# hall_shield.net
KiCad netlist of a schematic drawn in EAGLE
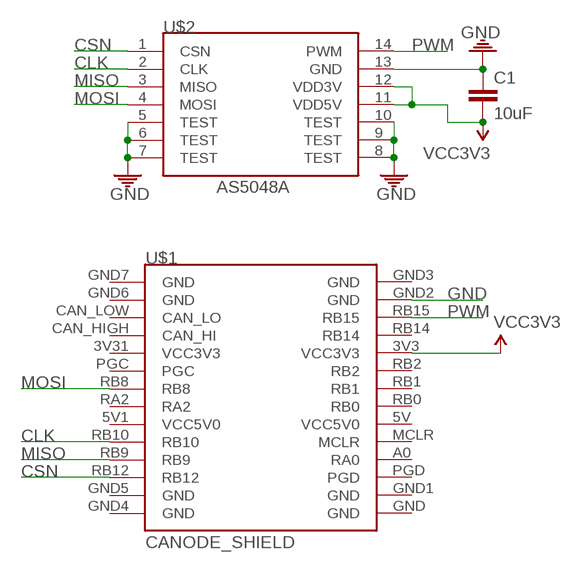
[diagram p0: schematic, sheet 1]

(export (version "E")
  (design (tool "Eeschema 10.0.6"))
  (components
    (comp (ref "C1")
      (value "10uF")
      (footprint "eagle-import:1206")
      (libsource (lib "eagle-import") (part "CAP1206"))
    )
    (comp (ref "U$1")
      (value "CANODE_SHIELD")
      (footprint "eagle-import:CANODE_SHIELD")
      (libsource (lib "eagle-import") (part "CANODE_SHIELD"))
    )
    (comp (ref "U$2")
      (value "AS5048A")
      (footprint "eagle-import:TSSOP14")
      (libsource (lib "eagle-import") (part "AS5048A"))
    )
  )
  (nets
    (net (code "1") (name "/CLK") (class "Default")
      (node (ref "U$1") (pin "RB10") (pinfunction "RB10_RB10") (pintype "bidirectional"))
      (node (ref "U$2") (pin "2") (pinfunction "CLK_2") (pintype "bidirectional"))
    )
    (net (code "2") (name "/CSN") (class "Default")
      (node (ref "U$1") (pin "RB12") (pinfunction "RB12_RB12") (pintype "bidirectional"))
      (node (ref "U$2") (pin "1") (pinfunction "CSN_1") (pintype "bidirectional"))
    )
    (net (code "3") (name "/MISO") (class "Default")
      (node (ref "U$1") (pin "RB9") (pinfunction "RB9_RB9") (pintype "bidirectional"))
      (node (ref "U$2") (pin "3") (pinfunction "MISO_3") (pintype "bidirectional"))
    )
    (net (code "4") (name "/MOSI") (class "Default")
      (node (ref "U$1") (pin "RB8") (pinfunction "RB8_RB8") (pintype "bidirectional"))
      (node (ref "U$2") (pin "4") (pinfunction "MOSI_4") (pintype "bidirectional"))
    )
    (net (code "5") (name "/PWM") (class "Default")
      (node (ref "U$1") (pin "RB15") (pinfunction "RB15_RB15") (pintype "bidirectional"))
      (node (ref "U$2") (pin "14") (pinfunction "PWM_14") (pintype "bidirectional"))
    )
    (net (code "6") (name "GND") (class "Default")
      (node (ref "C1") (pin "1") (pinfunction "1_1") (pintype "passive"))
      (node (ref "U$1") (pin "GND2") (pinfunction "GND_GND2") (pintype "bidirectional"))
      (node (ref "U$2") (pin "10") (pinfunction "TEST_10") (pintype "bidirectional"))
      (node (ref "U$2") (pin "13") (pinfunction "GND_13") (pintype "bidirectional"))
      (node (ref "U$2") (pin "5") (pinfunction "TEST_5") (pintype "bidirectional"))
      (node (ref "U$2") (pin "6") (pinfunction "TEST_6") (pintype "bidirectional"))
      (node (ref "U$2") (pin "7") (pinfunction "TEST_7") (pintype "bidirectional"))
      (node (ref "U$2") (pin "8") (pinfunction "TEST_8") (pintype "bidirectional"))
      (node (ref "U$2") (pin "9") (pinfunction "TEST_9") (pintype "bidirectional"))
    )
    (net (code "7") (name "VCC3V3") (class "Default")
      (node (ref "C1") (pin "2") (pinfunction "2_2") (pintype "passive"))
      (node (ref "U$1") (pin "3V3") (pinfunction "VCC3V3_3V3") (pintype "bidirectional"))
      (node (ref "U$2") (pin "11") (pinfunction "VDD5V_11") (pintype "bidirectional"))
      (node (ref "U$2") (pin "12") (pinfunction "VDD3V_12") (pintype "bidirectional"))
    )
    (net (code "8") (name "unconnected-(U$1-CAN_HI-PadCAN_HIGH)") (class "Default")
      (node (ref "U$1") (pin "CAN_HIGH") (pinfunction "CAN_HI_CAN_HIGH") (pintype "bidirectional"))
    )
    (net (code "9") (name "unconnected-(U$1-CAN_LO-PadCAN_LOW)") (class "Default")
      (node (ref "U$1") (pin "CAN_LOW") (pinfunction "CAN_LO_CAN_LOW") (pintype "bidirectional"))
    )
    (net (code "10") (name "unconnected-(U$1-GND-PadGND1)") (class "Default")
      (node (ref "U$1") (pin "GND1") (pinfunction "GND_GND1") (pintype "bidirectional"))
    )
    (net (code "11") (name "unconnected-(U$1-GND-PadGND3)") (class "Default")
      (node (ref "U$1") (pin "GND3") (pinfunction "GND_GND3") (pintype "bidirectional"))
    )
    (net (code "12") (name "unconnected-(U$1-GND-PadGND4)") (class "Default")
      (node (ref "U$1") (pin "GND4") (pinfunction "GND_GND4") (pintype "bidirectional"))
    )
    (net (code "13") (name "unconnected-(U$1-GND-PadGND5)") (class "Default")
      (node (ref "U$1") (pin "GND5") (pinfunction "GND_GND5") (pintype "bidirectional"))
    )
    (net (code "14") (name "unconnected-(U$1-GND-PadGND6)") (class "Default")
      (node (ref "U$1") (pin "GND6") (pinfunction "GND_GND6") (pintype "bidirectional"))
    )
    (net (code "15") (name "unconnected-(U$1-GND-PadGND7)") (class "Default")
      (node (ref "U$1") (pin "GND7") (pinfunction "GND_GND7") (pintype "bidirectional"))
    )
    (net (code "16") (name "unconnected-(U$1-PadGND)") (class "Default")
      (node (ref "U$1") (pin "GND") (pinfunction "GND_GND") (pintype "bidirectional"))
    )
    (net (code "17") (name "unconnected-(U$1-PadMCLR)") (class "Default")
      (node (ref "U$1") (pin "MCLR") (pinfunction "MCLR_MCLR") (pintype "bidirectional"))
    )
    (net (code "18") (name "unconnected-(U$1-PadPGC)") (class "Default")
      (node (ref "U$1") (pin "PGC") (pinfunction "PGC_PGC") (pintype "bidirectional"))
    )
    (net (code "19") (name "unconnected-(U$1-PadPGD)") (class "Default")
      (node (ref "U$1") (pin "PGD") (pinfunction "PGD_PGD") (pintype "bidirectional"))
    )
    (net (code "20") (name "unconnected-(U$1-PadRA2)") (class "Default")
      (node (ref "U$1") (pin "RA2") (pinfunction "RA2_RA2") (pintype "bidirectional"))
    )
    (net (code "21") (name "unconnected-(U$1-PadRB0)") (class "Default")
      (node (ref "U$1") (pin "RB0") (pinfunction "RB0_RB0") (pintype "bidirectional"))
    )
    (net (code "22") (name "unconnected-(U$1-PadRB1)") (class "Default")
      (node (ref "U$1") (pin "RB1") (pinfunction "RB1_RB1") (pintype "bidirectional"))
    )
    (net (code "23") (name "unconnected-(U$1-PadRB2)") (class "Default")
      (node (ref "U$1") (pin "RB2") (pinfunction "RB2_RB2") (pintype "bidirectional"))
    )
    (net (code "24") (name "unconnected-(U$1-PadRB14)") (class "Default")
      (node (ref "U$1") (pin "RB14") (pinfunction "RB14_RB14") (pintype "bidirectional"))
    )
    (net (code "25") (name "unconnected-(U$1-RA0-PadA0)") (class "Default")
      (node (ref "U$1") (pin "A0") (pinfunction "RA0_A0") (pintype "bidirectional"))
    )
    (net (code "26") (name "unconnected-(U$1-VCC3V3-Pad3V31)") (class "Default")
      (node (ref "U$1") (pin "3V31") (pinfunction "VCC3V3_3V31") (pintype "bidirectional"))
    )
    (net (code "27") (name "unconnected-(U$1-VCC5V0-Pad5V)") (class "Default")
      (node (ref "U$1") (pin "5V") (pinfunction "VCC5V0_5V") (pintype "bidirectional"))
    )
    (net (code "28") (name "unconnected-(U$1-VCC5V0-Pad5V1)") (class "Default")
      (node (ref "U$1") (pin "5V1") (pinfunction "VCC5V0_5V1") (pintype "bidirectional"))
    )
  )
)
